# Pill_Battery_Flex.net
KiCad netlist of a schematic drawn in Altium Designer
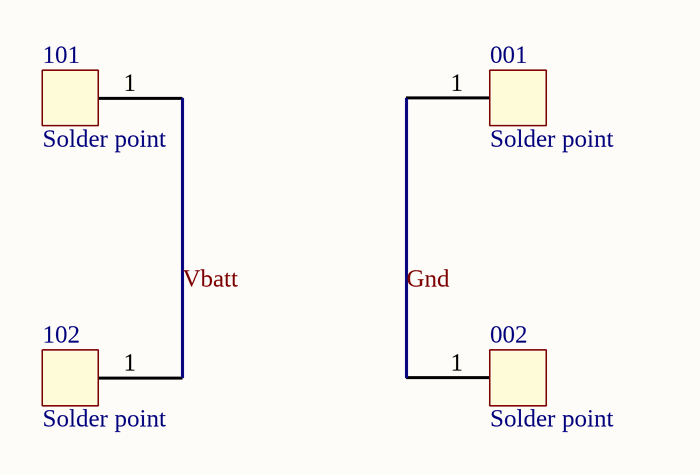
[diagram p0: Pill_Battery_Flex.SchDoc]

(export (version "E")
  (design (tool "Eeschema 10.0.6"))
  (components
    (comp (ref "001")
      (value "Solder point")
      (footprint "Pill_Flex_Via")
      (description "Gnd_boardside")
      (libsource (lib "") (part "Pill_flex_pad_1"))
    )
    (comp (ref "002")
      (value "Solder point")
      (footprint "Pill_Flex_Via")
      (description "Gnd_battside")
      (libsource (lib "") (part "Pill_flex_pad_1"))
    )
    (comp (ref "101")
      (value "Solder point")
      (footprint "Pill_Flex_Via")
      (description "Vbatt_boardside")
      (libsource (lib "Hello") (part "Pill_flex_pad"))
    )
    (comp (ref "102")
      (value "Solder point")
      (footprint "Pill_Flex_Via")
      (description "Vbatt_battside")
      (libsource (lib "Hello") (part "Pill_flex_pad"))
    )
  )
  (nets
    (net (code "1") (name "/Gnd") (class "Default")
      (node (ref "001") (pin "1") (pinfunction "1_1") (pintype "passive"))
      (node (ref "002") (pin "1") (pinfunction "1_1") (pintype "passive"))
    )
    (net (code "2") (name "/Vbatt") (class "Default")
      (node (ref "101") (pin "1") (pinfunction "1_1") (pintype "passive"))
      (node (ref "102") (pin "1") (pinfunction "1_1") (pintype "passive"))
    )
  )
)
